# openSX70_ALADDIN_V398B-SEEED_20180221.net
KiCad netlist of a schematic drawn in EAGLE
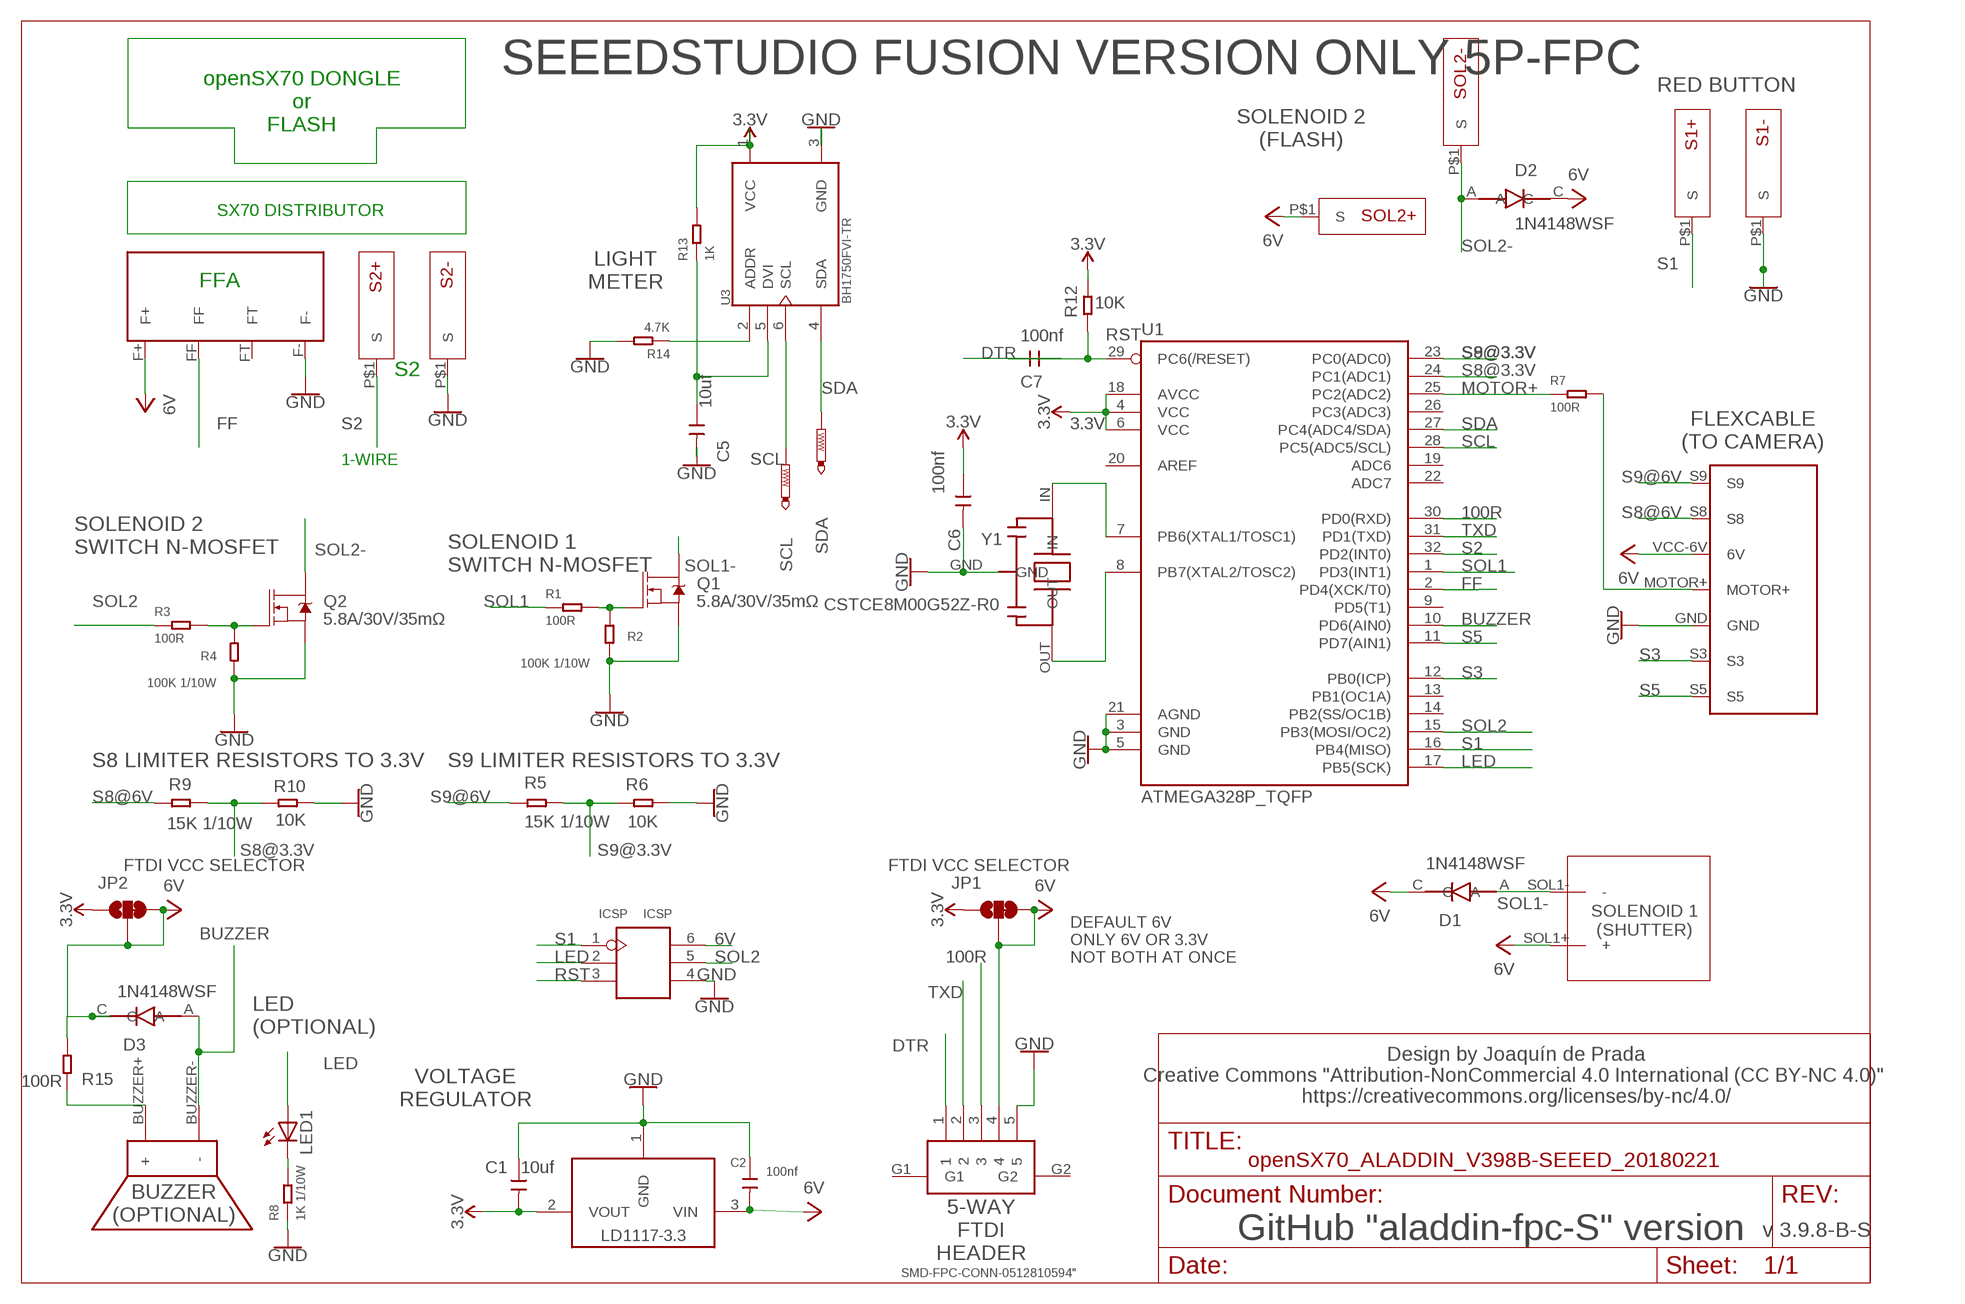
[diagram p0: schematic, sheet 1]

(export (version "E")
  (design (tool "Eeschema 10.0.6"))
  (components
    (comp (ref "C1")
      (value "10uf")
      (footprint "eagle-import:C0603")
      (fields (field (name "MPN") "CC0603KRX5R6BB106"))
      (libsource (lib "eagle-import") (part "CERAMIC-10UF-10V-10%-X5R(0603)"))
    )
    (comp (ref "C2")
      (value "100nf")
      (footprint "eagle-import:C0603")
      (fields (field (name "MPN") "CC0603KRX7R9BB104"))
      (libsource (lib "eagle-import") (part "CERAMIC-100NF-50V-10%-X7R(0603)"))
    )
    (comp (ref "C5")
      (value "10uf")
      (footprint "eagle-import:C0603")
      (fields (field (name "MPN") "CC0603KRX5R6BB106"))
      (libsource (lib "eagle-import") (part "CERAMIC-10UF-10V-10%-X5R(0603)"))
    )
    (comp (ref "C6")
      (value "100nf")
      (footprint "eagle-import:C0603")
      (fields (field (name "MPN") "CC0603KRX7R9BB104"))
      (libsource (lib "eagle-import") (part "CERAMIC-100NF-50V-10%-X7R(0603)"))
    )
    (comp (ref "C7")
      (value "100nf")
      (footprint "eagle-import:C0603")
      (fields (field (name "MPN") "CC0603KRX7R9BB104"))
      (libsource (lib "eagle-import") (part "CERAMIC-100NF-50V-10%-X7R(0603)"))
    )
    (comp (ref "D1")
      (value "1N4148WSF")
      (footprint "eagle-import:SODFL2512X100N")
      (fields (field (name "MANUFACTURER") "Fairchild Semiconductor"))
      (libsource (lib "eagle-import") (part "1N4148WS"))
    )
    (comp (ref "D2")
      (value "1N4148WSF")
      (footprint "eagle-import:SODFL2512X100N")
      (fields (field (name "MANUFACTURER") "Fairchild Semiconductor"))
      (libsource (lib "eagle-import") (part "1N4148WS"))
    )
    (comp (ref "D3")
      (value "1N4148WSF")
      (footprint "eagle-import:SODFL2512X100N")
      (fields (field (name "MANUFACTURER") "Fairchild Semiconductor"))
      (libsource (lib "eagle-import") (part "1N4148WS"))
    )
    (comp (ref "ICSP")
      (value "ICSP")
      (footprint "eagle-import:H2X3-2.54")
      (libsource (lib "eagle-import") (part "ICSP"))
    )
    (comp (ref "JP1")
      (value "FTDI VCC SELECTOR")
      (footprint "eagle-import:SMT-JUMPER_3_1-NC_TRACE_SILK")
      (libsource (lib "eagle-import") (part "JUMPER-SMT_3_1-NC_TRACE_SILK"))
    )
    (comp (ref "JP2")
      (value "FTDI VCC SELECTOR")
      (footprint "eagle-import:SMT-JUMPER_3_1-NC_TRACE_SILK")
      (libsource (lib "eagle-import") (part "JUMPER-SMT_3_1-NC_TRACE_SILK"))
    )
    (comp (ref "LD11172.5V")
      (value "LD1117 2.5V")
      (footprint "eagle-import:SOT223")
      (fields (field (name "MF") "Advanced Monolithic Systems") (field (name "MP") "AMS1117-5.0"))
      (libsource (lib "eagle-import") (part "LD1117-3.3"))
    )
    (comp (ref "LED1")
      (value "LEDCHIPLED_0805")
      (footprint "eagle-import:CHIPLED_0805")
      (libsource (lib "eagle-import") (part "LEDCHIPLED_0805"))
    )
    (comp (ref "Q1")
      (value "5.8A/30V/35mΩ")
      (footprint "eagle-import:SOT23-3")
      (libsource (lib "eagle-import") (part "MOSFET-NCH-AO3404A"))
    )
    (comp (ref "Q2")
      (value "5.8A/30V/35mΩ")
      (footprint "eagle-import:SOT23-3")
      (libsource (lib "eagle-import") (part "MOSFET-NCH-AO3404A"))
    )
    (comp (ref "R1")
      (value "100R")
      (footprint "eagle-import:R0603")
      (fields (field (name "MPN") "RC0603JR-07100RL"))
      (libsource (lib "eagle-import") (part "SMD-RES-100R-5%-1/10W(0603)"))
    )
    (comp (ref "R2")
      (value "100K 1/10W")
      (footprint "eagle-import:R0603")
      (fields (field (name "MPN") "RC0603JR-07100KL"))
      (libsource (lib "eagle-import") (part "SMD-RES-100K-5%-1/10W(0603)"))
    )
    (comp (ref "R3")
      (value "100R")
      (footprint "eagle-import:R0603")
      (fields (field (name "MPN") "RC0603JR-07100RL"))
      (libsource (lib "eagle-import") (part "SMD-RES-100R-5%-1/10W(0603)"))
    )
    (comp (ref "R4")
      (value "100K 1/10W")
      (footprint "eagle-import:R0603")
      (fields (field (name "MPN") "RC0603JR-07100KL"))
      (libsource (lib "eagle-import") (part "SMD-RES-100K-5%-1/10W(0603)"))
    )
    (comp (ref "R5")
      (value "15K 1/10W")
      (footprint "eagle-import:R0603")
      (fields (field (name "MPN") "RC0603FR-0715KL"))
      (libsource (lib "eagle-import") (part "SMD-RES-15K-1%-1/10W(0603)"))
    )
    (comp (ref "R6")
      (value "10K")
      (footprint "eagle-import:R0603")
      (fields (field (name "MPN") "RC0603FR-0710KL"))
      (libsource (lib "eagle-import") (part "SMD-RES-10K-1%-1/10W(0603)"))
    )
    (comp (ref "R7")
      (value "100R")
      (footprint "eagle-import:R0603")
      (fields (field (name "MPN") "RC0603JR-07100RL"))
      (libsource (lib "eagle-import") (part "SMD-RES-100R-5%-1/10W(0603)"))
    )
    (comp (ref "R8")
      (value "1K 1/10W")
      (footprint "eagle-import:R0603")
      (fields (field (name "MPN") "RC0603JR-071KL"))
      (libsource (lib "eagle-import") (part "SMD-RES-1K-5%-1/10W(0603)"))
    )
    (comp (ref "R9")
      (value "15K 1/10W")
      (footprint "eagle-import:R0603")
      (fields (field (name "MPN") "RC0603FR-0715KL"))
      (libsource (lib "eagle-import") (part "SMD-RES-15K-1%-1/10W(0603)"))
    )
    (comp (ref "R10")
      (value "10K")
      (footprint "eagle-import:R0603")
      (fields (field (name "MPN") "RC0603FR-0710KL"))
      (libsource (lib "eagle-import") (part "SMD-RES-10K-1%-1/10W(0603)"))
    )
    (comp (ref "R12")
      (value "10K")
      (footprint "eagle-import:R0603")
      (fields (field (name "MPN") "RC0603FR-0710KL"))
      (libsource (lib "eagle-import") (part "SMD-RES-10K-1%-1/10W(0603)"))
    )
    (comp (ref "R13")
      (value "1K")
      (footprint "eagle-import:R0603")
      (fields (field (name "MPN") "RC0603FR-071KL"))
      (libsource (lib "eagle-import") (part "SMD-RES-1K-1%-1/10W(0603)"))
    )
    (comp (ref "R14")
      (value "4.7K")
      (footprint "eagle-import:R0603")
      (fields (field (name "MPN") "RC0603JR-074K7L"))
      (libsource (lib "eagle-import") (part "SMD-RES-4.7K-5%-1/10W(0603)"))
    )
    (comp (ref "R15")
      (value "100R")
      (footprint "eagle-import:R0603")
      (fields (field (name "MPN") "RC0603JR-07100RL"))
      (libsource (lib "eagle-import") (part "SMD-RES-100R-5%-1/10W(0603)"))
    )
    (comp (ref "S1+")
      (value "SX70-S-PAD-NEW")
      (footprint "eagle-import:SX70-S-PAD2")
      (libsource (lib "eagle-import") (part "SX70-S-PAD-NEW"))
    )
    (comp (ref "S1-")
      (value "SX70-S-PAD-NEW")
      (footprint "eagle-import:SX70-S-PAD2")
      (libsource (lib "eagle-import") (part "SX70-S-PAD-NEW"))
    )
    (comp (ref "S2+")
      (value "SX70-S-PAD-NEW")
      (footprint "eagle-import:SX70-S-PAD2")
      (libsource (lib "eagle-import") (part "SX70-S-PAD-NEW"))
    )
    (comp (ref "S2-")
      (value "SX70-S-PAD-NEW")
      (footprint "eagle-import:SX70-S-PAD2")
      (libsource (lib "eagle-import") (part "SX70-S-PAD-NEW"))
    )
    (comp (ref "SCL")
      (value "PTR1TP08R")
      (footprint "eagle-import:TP08R")
      (libsource (lib "eagle-import") (part "PTR1TP08R"))
    )
    (comp (ref "SDA")
      (value "PTR1TP08R")
      (footprint "eagle-import:TP08R")
      (libsource (lib "eagle-import") (part "PTR1TP08R"))
    )
    (comp (ref "SOL1")
      (value "SX70-SOLENOID1-2PADS")
      (footprint "eagle-import:SX70-SOLENOID1-2")
      (libsource (lib "eagle-import") (part "SX70-SOLENOID1-2PADS"))
    )
    (comp (ref "SOL2+")
      (value "SX70-S-PAD-NEW")
      (footprint "eagle-import:SX70-S-PAD2")
      (libsource (lib "eagle-import") (part "SX70-S-PAD-NEW"))
    )
    (comp (ref "SOL2-")
      (value "SX70-S-PAD-NEW")
      (footprint "eagle-import:SX70-S-PAD2")
      (libsource (lib "eagle-import") (part "SX70-S-PAD-NEW"))
    )
    (comp (ref "U$1")
      (value "SX70-7-PAD")
      (footprint "eagle-import:SX70-7-PAD")
      (libsource (lib "eagle-import") (part "SX70-7-PAD"))
    )
    (comp (ref "U$2")
      (value "FFA")
      (footprint "eagle-import:FFA-PAD-PACKAGE")
      (libsource (lib "eagle-import") (part "SX70-FFA-PAD"))
    )
    (comp (ref "U$3")
      (value "CSET8-5G_V2")
      (footprint "eagle-import:CSET8-5G_PACKAGE")
      (libsource (lib "eagle-import") (part "CSET8-5G_V2"))
    )
    (comp (ref "U$4")
      (value "SMD-FPC-CONN-0512810594\"")
      (footprint "eagle-import:51281-0594")
      (libsource (lib "eagle-import") (part "SMD-FPC-CONN-0512810594{dblquote}"))
    )
    (comp (ref "U1")
      (value "ATMEGA328P_TQFP")
      (footprint "eagle-import:TQFP32-08")
      (libsource (lib "eagle-import") (part "ATMEGA328P_TQFP"))
    )
    (comp (ref "U3")
      (value "BH1750FVI-TR")
      (footprint "eagle-import:SOTFL50P300X75-6N")
      (fields (field (name "MF") "Rohm"))
      (libsource (lib "eagle-import") (part "BH1750FVI-TR"))
    )
    (comp (ref "Y1")
      (value "CSTCE8M00G52Z-R0")
      (footprint "eagle-import:CFP95P160X100-3N")
      (fields (field (name "MF") "Murata") (field (name "MP") "CSTCE16M0V53-R0"))
      (libsource (lib "eagle-import") (part "CSTCE16M0V53-R0"))
    )
  )
  (nets
    (net (code "1") (name "/100R") (class "Default")
      (node (ref "U$4") (pin "3") (pinfunction "3_3") (pintype "bidirectional"))
      (node (ref "U1") (pin "30") (pinfunction "PD0(RXD)_30") (pintype "bidirectional"))
    )
    (net (code "2") (name "/BUZZER") (class "Default")
      (node (ref "D3") (pin "A") (pinfunction "A_A") (pintype "passive"))
      (node (ref "U$3") (pin "BUZZER-") (pinfunction "-_BUZZER-") (pintype "bidirectional"))
      (node (ref "U1") (pin "10") (pinfunction "PD6(AIN0)_10") (pintype "bidirectional"))
    )
    (net (code "3") (name "/DTR") (class "Default")
      (node (ref "C7") (pin "1") (pinfunction "1_1") (pintype "passive"))
      (node (ref "U$4") (pin "1") (pinfunction "1_1") (pintype "bidirectional"))
    )
    (net (code "4") (name "/FF") (class "Default")
      (node (ref "U$2") (pin "FF") (pinfunction "FF_FF") (pintype "bidirectional"))
      (node (ref "U1") (pin "2") (pinfunction "PD4(XCK/T0)_2") (pintype "bidirectional"))
    )
    (net (code "5") (name "/LED") (class "Default")
      (node (ref "ICSP") (pin "2") (pinfunction "SCK_2") (pintype "bidirectional"))
      (node (ref "LED1") (pin "A") (pinfunction "A_A") (pintype "passive"))
      (node (ref "U1") (pin "17") (pinfunction "PB5(SCK)_17") (pintype "bidirectional"))
    )
    (net (code "6") (name "/MOTOR+") (class "Default")
      (node (ref "R7") (pin "1") (pinfunction "1_1") (pintype "passive"))
      (node (ref "U1") (pin "25") (pinfunction "PC2(ADC2)_25") (pintype "bidirectional"))
    )
    (net (code "7") (name "/RST") (class "Default")
      (node (ref "C7") (pin "2") (pinfunction "2_2") (pintype "passive"))
      (node (ref "ICSP") (pin "3") (pinfunction "RST_3") (pintype "bidirectional"))
      (node (ref "R12") (pin "1") (pinfunction "1_1") (pintype "passive"))
      (node (ref "U1") (pin "29") (pinfunction "PC6(/RESET)_29") (pintype "bidirectional"))
    )
    (net (code "8") (name "/S1") (class "Default")
      (node (ref "ICSP") (pin "1") (pinfunction "MISO_1") (pintype "bidirectional"))
      (node (ref "S1+") (pin "P$1") (pinfunction "S_P$1") (pintype "bidirectional"))
      (node (ref "U1") (pin "16") (pinfunction "PB4(MISO)_16") (pintype "bidirectional"))
    )
    (net (code "9") (name "/S2") (class "Default")
      (node (ref "S2+") (pin "P$1") (pinfunction "S_P$1") (pintype "bidirectional"))
      (node (ref "U1") (pin "32") (pinfunction "PD2(INT0)_32") (pintype "bidirectional"))
    )
    (net (code "10") (name "/S3") (class "Default")
      (node (ref "U$1") (pin "S3") (pinfunction "S3_S3") (pintype "bidirectional"))
      (node (ref "U1") (pin "12") (pinfunction "PB0(ICP)_12") (pintype "bidirectional"))
    )
    (net (code "11") (name "/S5") (class "Default")
      (node (ref "U$1") (pin "S5") (pinfunction "S5_S5") (pintype "bidirectional"))
      (node (ref "U1") (pin "11") (pinfunction "PD7(AIN1)_11") (pintype "bidirectional"))
    )
    (net (code "12") (name "/S8@3.3V") (class "Default")
      (node (ref "R10") (pin "1") (pinfunction "1_1") (pintype "passive"))
      (node (ref "R9") (pin "2") (pinfunction "2_2") (pintype "passive"))
      (node (ref "U1") (pin "24") (pinfunction "PC1(ADC1)_24") (pintype "bidirectional"))
    )
    (net (code "13") (name "/S8@6V") (class "Default")
      (node (ref "R9") (pin "1") (pinfunction "1_1") (pintype "passive"))
      (node (ref "U$1") (pin "S8") (pinfunction "S8_S8") (pintype "bidirectional"))
    )
    (net (code "14") (name "/S9@3.3V") (class "Default")
      (node (ref "R5") (pin "2") (pinfunction "2_2") (pintype "passive"))
      (node (ref "R6") (pin "1") (pinfunction "1_1") (pintype "passive"))
      (node (ref "U1") (pin "23") (pinfunction "PC0(ADC0)_23") (pintype "bidirectional"))
    )
    (net (code "15") (name "/S9@6V") (class "Default")
      (node (ref "R5") (pin "1") (pinfunction "1_1") (pintype "passive"))
      (node (ref "U$1") (pin "S9") (pinfunction "S9_S9") (pintype "bidirectional"))
    )
    (net (code "16") (name "/SCL") (class "Default")
      (node (ref "SCL") (pin "TP") (pinfunction "TP_TP") (pintype "input"))
      (node (ref "U1") (pin "28") (pinfunction "PC5(ADC5/SCL)_28") (pintype "bidirectional"))
      (node (ref "U3") (pin "6") (pinfunction "SCL_6") (pintype "input"))
    )
    (net (code "17") (name "/SDA") (class "Default")
      (node (ref "SDA") (pin "TP") (pinfunction "TP_TP") (pintype "input"))
      (node (ref "U1") (pin "27") (pinfunction "PC4(ADC4/SDA)_27") (pintype "bidirectional"))
      (node (ref "U3") (pin "4") (pinfunction "SDA_4") (pintype "bidirectional"))
    )
    (net (code "18") (name "/SOL1") (class "Default")
      (node (ref "R1") (pin "1") (pinfunction "1_1") (pintype "passive"))
      (node (ref "U1") (pin "1") (pinfunction "PD3(INT1)_1") (pintype "bidirectional"))
    )
    (net (code "19") (name "/SOL1-") (class "Default")
      (node (ref "D1") (pin "A") (pinfunction "A_A") (pintype "passive"))
      (node (ref "Q1") (pin "3") (pinfunction "D_3") (pintype "bidirectional"))
      (node (ref "SOL1") (pin "SOL1-") (pinfunction "-_SOL1-") (pintype "bidirectional"))
    )
    (net (code "20") (name "/SOL2") (class "Default")
      (node (ref "ICSP") (pin "5") (pinfunction "MOSI_5") (pintype "bidirectional"))
      (node (ref "R3") (pin "1") (pinfunction "1_1") (pintype "passive"))
      (node (ref "U1") (pin "15") (pinfunction "PB3(MOSI/OC2)_15") (pintype "bidirectional"))
    )
    (net (code "21") (name "/SOL2-") (class "Default")
      (node (ref "D2") (pin "A") (pinfunction "A_A") (pintype "passive"))
      (node (ref "Q2") (pin "3") (pinfunction "D_3") (pintype "bidirectional"))
      (node (ref "SOL2-") (pin "P$1") (pinfunction "S_P$1") (pintype "bidirectional"))
    )
    (net (code "22") (name "/TXD") (class "Default")
      (node (ref "U$4") (pin "2") (pinfunction "2_2") (pintype "bidirectional"))
      (node (ref "U1") (pin "31") (pinfunction "PD1(TXD)_31") (pintype "bidirectional"))
    )
    (net (code "23") (name "3.3V") (class "Default")
      (node (ref "C1") (pin "2") (pinfunction "2_2") (pintype "passive"))
      (node (ref "C6") (pin "1") (pinfunction "1_1") (pintype "passive"))
      (node (ref "JP1") (pin "1") (pinfunction "1_1") (pintype "passive"))
      (node (ref "JP2") (pin "1") (pinfunction "1_1") (pintype "passive"))
      (node (ref "LD11172.5V") (pin "2") (pinfunction "VOUT_2") (pintype "bidirectional"))
      (node (ref "R12") (pin "2") (pinfunction "2_2") (pintype "passive"))
      (node (ref "R13") (pin "2") (pinfunction "2_2") (pintype "passive"))
      (node (ref "U1") (pin "18") (pinfunction "AVCC_18") (pintype "bidirectional"))
      (node (ref "U1") (pin "4") (pinfunction "VCC_4") (pintype "bidirectional"))
      (node (ref "U1") (pin "6") (pinfunction "VCC_6") (pintype "bidirectional"))
      (node (ref "U3") (pin "1") (pinfunction "VCC_1") (pintype "power_in"))
    )
    (net (code "24") (name "6V") (class "Default")
      (node (ref "C2") (pin "2") (pinfunction "2_2") (pintype "passive"))
      (node (ref "D1") (pin "C") (pinfunction "C_C") (pintype "passive"))
      (node (ref "D2") (pin "C") (pinfunction "C_C") (pintype "passive"))
      (node (ref "D3") (pin "C") (pinfunction "C_C") (pintype "passive"))
      (node (ref "ICSP") (pin "6") (pinfunction "VCC_6") (pintype "bidirectional"))
      (node (ref "JP1") (pin "2") (pinfunction "2_2") (pintype "passive"))
      (node (ref "JP1") (pin "3") (pinfunction "3_3") (pintype "passive"))
      (node (ref "JP2") (pin "2") (pinfunction "2_2") (pintype "passive"))
      (node (ref "JP2") (pin "3") (pinfunction "3_3") (pintype "passive"))
      (node (ref "LD11172.5V") (pin "3") (pinfunction "VIN_3") (pintype "bidirectional"))
      (node (ref "R15") (pin "2") (pinfunction "2_2") (pintype "passive"))
      (node (ref "SOL1") (pin "SOL1+") (pinfunction "+_SOL1+") (pintype "bidirectional"))
      (node (ref "SOL2+") (pin "P$1") (pinfunction "S_P$1") (pintype "bidirectional"))
      (node (ref "U$1") (pin "VCC-6V") (pinfunction "6V_VCC-6V") (pintype "bidirectional"))
      (node (ref "U$2") (pin "F+") (pinfunction "F+_F+") (pintype "bidirectional"))
      (node (ref "U$4") (pin "4") (pinfunction "4_4") (pintype "bidirectional"))
    )
    (net (code "25") (name "GND") (class "Default")
      (node (ref "C1") (pin "1") (pinfunction "1_1") (pintype "passive"))
      (node (ref "C2") (pin "1") (pinfunction "1_1") (pintype "passive"))
      (node (ref "C5") (pin "2") (pinfunction "2_2") (pintype "passive"))
      (node (ref "C6") (pin "2") (pinfunction "2_2") (pintype "passive"))
      (node (ref "ICSP") (pin "4") (pinfunction "GND_4") (pintype "bidirectional"))
      (node (ref "LD11172.5V") (pin "1") (pinfunction "GND_1") (pintype "bidirectional"))
      (node (ref "Q1") (pin "2") (pinfunction "S_2") (pintype "bidirectional"))
      (node (ref "Q2") (pin "2") (pinfunction "S_2") (pintype "bidirectional"))
      (node (ref "R10") (pin "2") (pinfunction "2_2") (pintype "passive"))
      (node (ref "R14") (pin "2") (pinfunction "2_2") (pintype "passive"))
      (node (ref "R2") (pin "1") (pinfunction "1_1") (pintype "passive"))
      (node (ref "R4") (pin "1") (pinfunction "1_1") (pintype "passive"))
      (node (ref "R6") (pin "2") (pinfunction "2_2") (pintype "passive"))
      (node (ref "R8") (pin "1") (pinfunction "1_1") (pintype "passive"))
      (node (ref "S1-") (pin "P$1") (pinfunction "S_P$1") (pintype "bidirectional"))
      (node (ref "S2-") (pin "P$1") (pinfunction "S_P$1") (pintype "bidirectional"))
      (node (ref "U$1") (pin "GND") (pinfunction "GND_GND") (pintype "bidirectional"))
      (node (ref "U$2") (pin "F-") (pinfunction "F-_F-") (pintype "bidirectional"))
      (node (ref "U$4") (pin "5") (pinfunction "5_5") (pintype "bidirectional"))
      (node (ref "U1") (pin "21") (pinfunction "AGND_21") (pintype "bidirectional"))
      (node (ref "U1") (pin "3") (pinfunction "GND_3") (pintype "bidirectional"))
      (node (ref "U1") (pin "5") (pinfunction "GND_5") (pintype "bidirectional"))
      (node (ref "U3") (pin "3") (pinfunction "GND_3") (pintype "power_in"))
      (node (ref "Y1") (pin "GND") (pinfunction "GND_GND") (pintype "passive"))
    )
    (net (code "26") (name "Net-(LED1-PadC)") (class "Default")
      (node (ref "LED1") (pin "C") (pinfunction "C_C") (pintype "passive"))
      (node (ref "R8") (pin "2") (pinfunction "2_2") (pintype "passive"))
    )
    (net (code "27") (name "Net-(Q1-G)") (class "Default")
      (node (ref "Q1") (pin "1") (pinfunction "G_1") (pintype "bidirectional"))
      (node (ref "R1") (pin "2") (pinfunction "2_2") (pintype "passive"))
      (node (ref "R2") (pin "2") (pinfunction "2_2") (pintype "passive"))
    )
    (net (code "28") (name "Net-(Q2-G)") (class "Default")
      (node (ref "Q2") (pin "1") (pinfunction "G_1") (pintype "bidirectional"))
      (node (ref "R3") (pin "2") (pinfunction "2_2") (pintype "passive"))
      (node (ref "R4") (pin "2") (pinfunction "2_2") (pintype "passive"))
    )
    (net (code "29") (name "Net-(R7-Pad2)") (class "Default")
      (node (ref "R7") (pin "2") (pinfunction "2_2") (pintype "passive"))
      (node (ref "U$1") (pin "MOTOR+") (pinfunction "MOTOR+_MOTOR+") (pintype "bidirectional"))
    )
    (net (code "30") (name "Net-(U$3-+)") (class "Default")
      (node (ref "R15") (pin "1") (pinfunction "1_1") (pintype "passive"))
      (node (ref "U$3") (pin "BUZZER+") (pinfunction "+_BUZZER+") (pintype "bidirectional"))
    )
    (net (code "31") (name "Net-(U1-PB6(XTAL1{slash}TOSC1))") (class "Default")
      (node (ref "U1") (pin "7") (pinfunction "PB6(XTAL1/TOSC1)_7") (pintype "bidirectional"))
      (node (ref "Y1") (pin "IN") (pinfunction "IN_IN") (pintype "input"))
    )
    (net (code "32") (name "Net-(U1-PB7(XTAL2{slash}TOSC2))") (class "Default")
      (node (ref "U1") (pin "8") (pinfunction "PB7(XTAL2/TOSC2)_8") (pintype "bidirectional"))
      (node (ref "Y1") (pin "OUT") (pinfunction "OUT_OUT") (pintype "output"))
    )
    (net (code "33") (name "Net-(U3-ADDR)") (class "Default")
      (node (ref "R14") (pin "1") (pinfunction "1_1") (pintype "passive"))
      (node (ref "U3") (pin "2") (pinfunction "ADDR_2") (pintype "input"))
    )
    (net (code "34") (name "Net-(U3-DVI)") (class "Default")
      (node (ref "C5") (pin "1") (pinfunction "1_1") (pintype "passive"))
      (node (ref "R13") (pin "1") (pinfunction "1_1") (pintype "passive"))
      (node (ref "U3") (pin "5") (pinfunction "DVI_5") (pintype "input"))
    )
    (net (code "35") (name "unconnected-(U$2-PadFT)") (class "Default")
      (node (ref "U$2") (pin "FT") (pinfunction "FT_FT") (pintype "bidirectional"))
    )
    (net (code "36") (name "unconnected-(U$4-PadG1)") (class "Default")
      (node (ref "U$4") (pin "G1") (pinfunction "G1_G1") (pintype "bidirectional"))
    )
    (net (code "37") (name "unconnected-(U$4-PadG2)") (class "Default")
      (node (ref "U$4") (pin "G2") (pinfunction "G2_G2") (pintype "bidirectional"))
    )
    (net (code "38") (name "unconnected-(U1-ADC6-Pad19)") (class "Default")
      (node (ref "U1") (pin "19") (pinfunction "ADC6_19") (pintype "bidirectional"))
    )
    (net (code "39") (name "unconnected-(U1-ADC7-Pad22)") (class "Default")
      (node (ref "U1") (pin "22") (pinfunction "ADC7_22") (pintype "bidirectional"))
    )
    (net (code "40") (name "unconnected-(U1-AREF-Pad20)") (class "Default")
      (node (ref "U1") (pin "20") (pinfunction "AREF_20") (pintype "bidirectional"))
    )
    (net (code "41") (name "unconnected-(U1-PB1(OC1A)-Pad13)") (class "Default")
      (node (ref "U1") (pin "13") (pinfunction "PB1(OC1A)_13") (pintype "bidirectional"))
    )
    (net (code "42") (name "unconnected-(U1-PB2(SS{slash}OC1B)-Pad14)") (class "Default")
      (node (ref "U1") (pin "14") (pinfunction "PB2(SS/OC1B)_14") (pintype "bidirectional"))
    )
    (net (code "43") (name "unconnected-(U1-PC3(ADC3)-Pad26)") (class "Default")
      (node (ref "U1") (pin "26") (pinfunction "PC3(ADC3)_26") (pintype "bidirectional"))
    )
    (net (code "44") (name "unconnected-(U1-PD5(T1)-Pad9)") (class "Default")
      (node (ref "U1") (pin "9") (pinfunction "PD5(T1)_9") (pintype "bidirectional"))
    )
  )
)
